# IO.net
KiCad netlist of a schematic drawn in Altium Designer
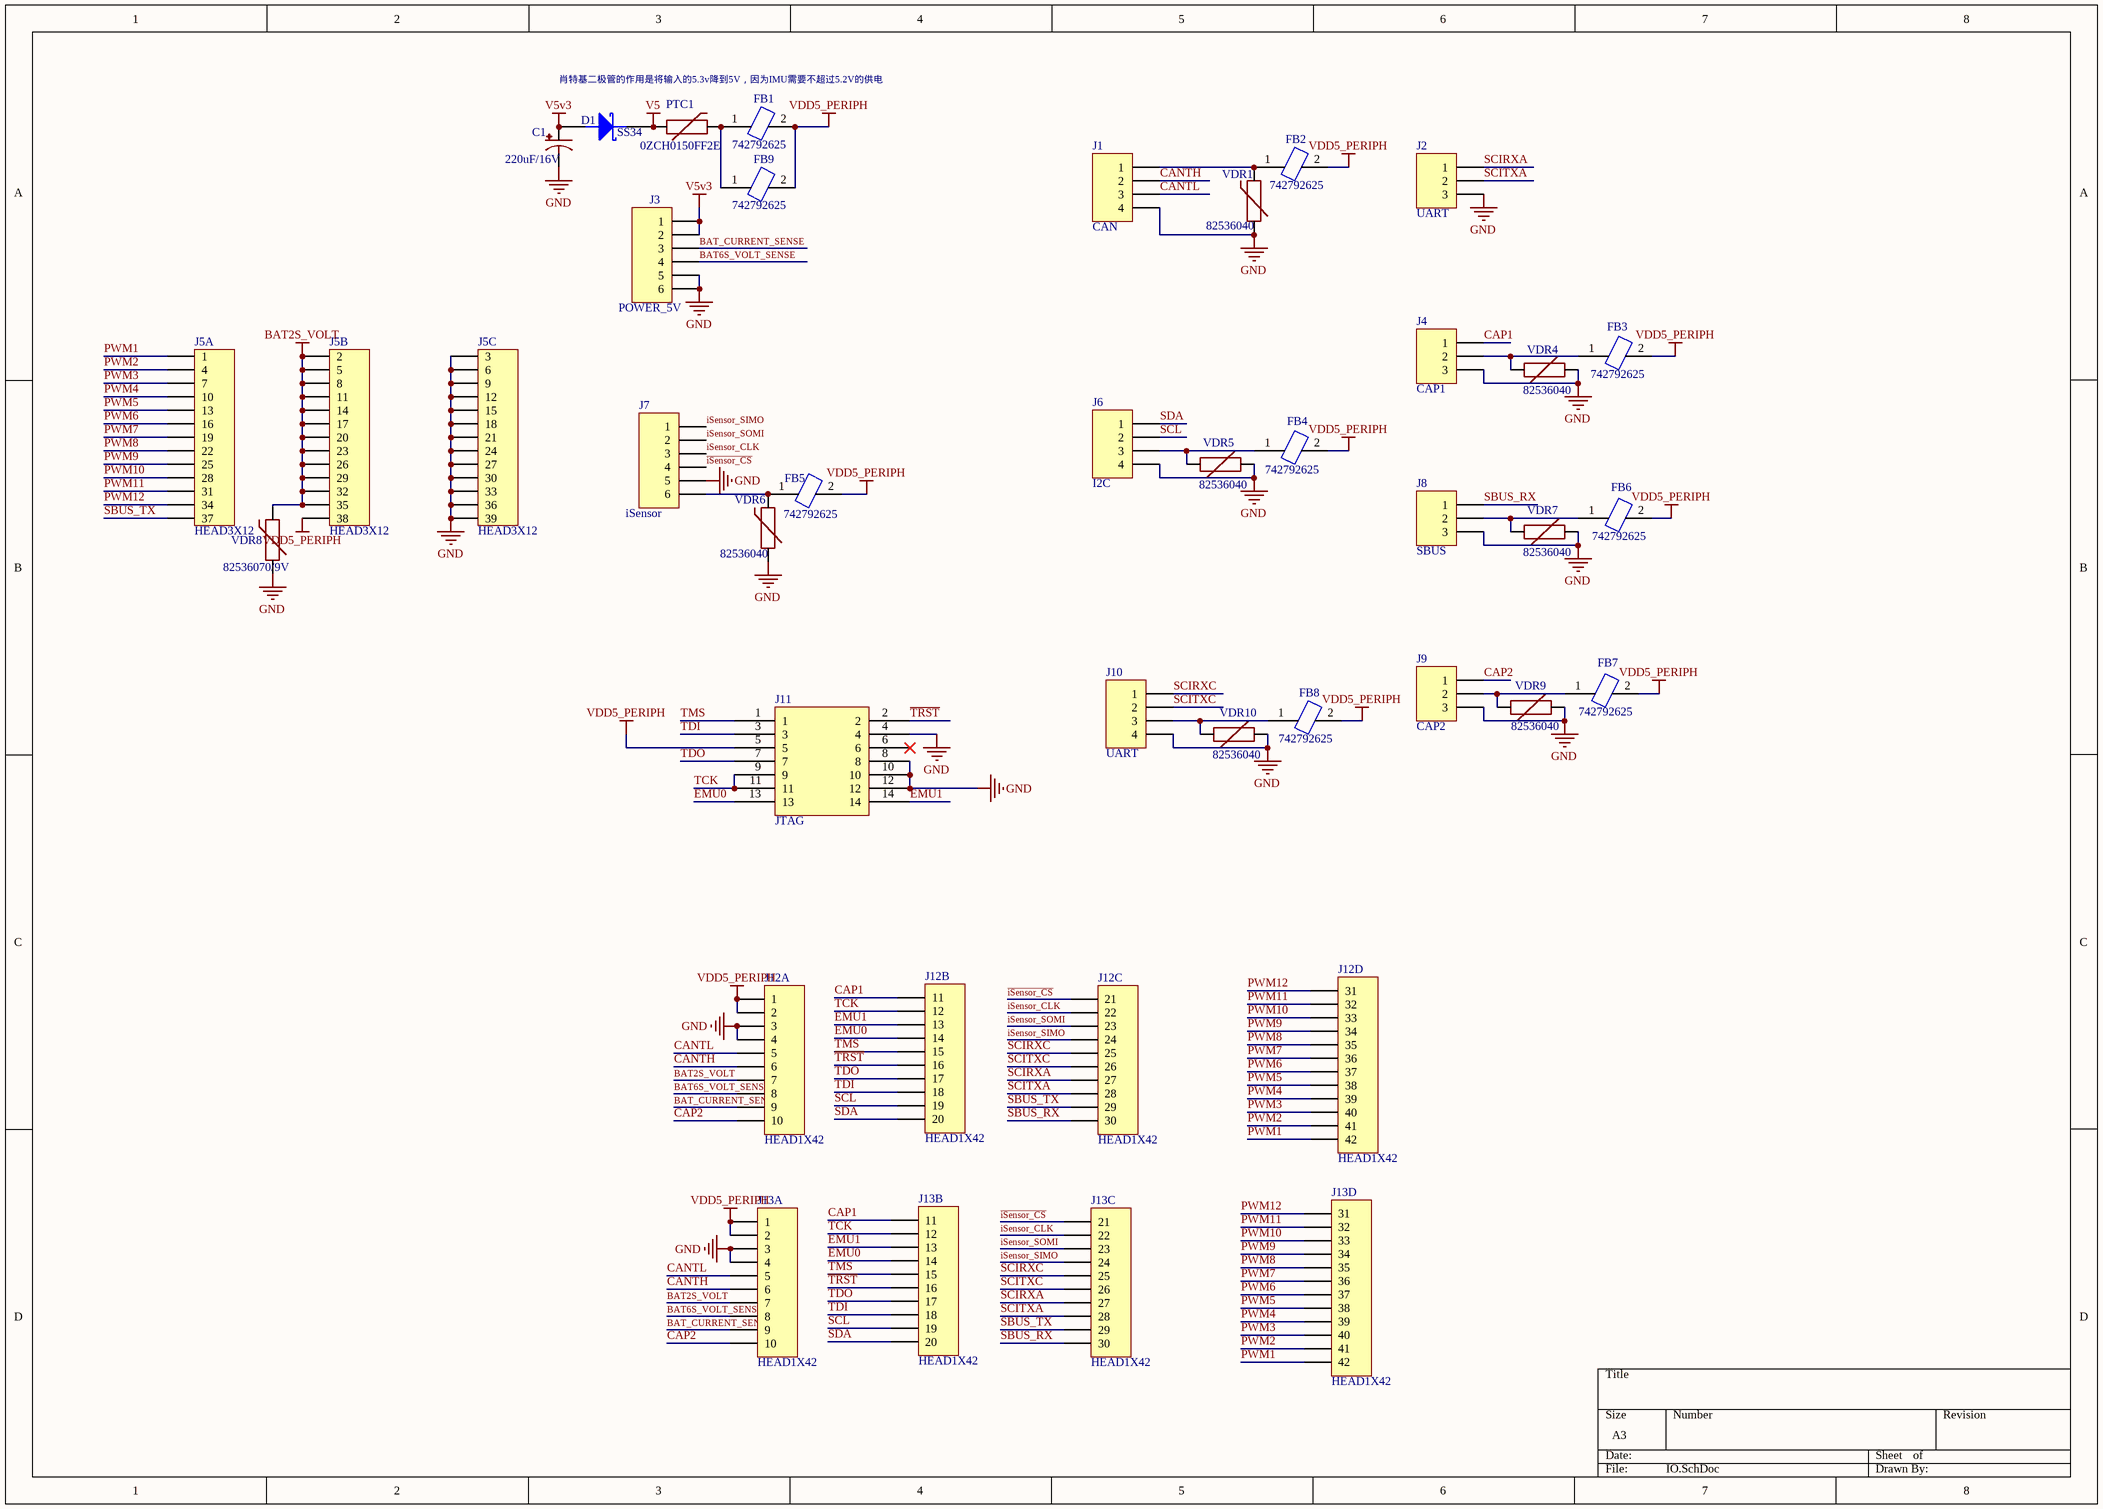
[diagram p0: IO.SchDoc]

(export (version "E")
  (design (tool "Eeschema 10.0.6"))
  (components
    (comp (ref "C1")
      (value "220uF/16V")
      (footprint "6.3*7.7/H/220u")
      (libsource (lib "研发中心原理图库文件") (part "C-POLAR"))
    )
    (comp (ref "D1")
      (value "SS34")
      (footprint "SMB/DO-214AA")
      (libsource (lib "研发中心原理图库文件") (part "DIODE SCHOTTKY"))
    )
    (comp (ref "FB1")
      (value "742792625")
      (footprint "研发中心PCB库文件:0603-FB")
      (libsource (lib "研发中心原理图库文件") (part "FB"))
    )
    (comp (ref "FB2")
      (value "742792625")
      (footprint "研发中心PCB库文件:0603-FB")
      (libsource (lib "研发中心原理图库文件") (part "FB"))
    )
    (comp (ref "FB3")
      (value "742792625")
      (footprint "研发中心PCB库文件:0603-FB")
      (libsource (lib "研发中心原理图库文件") (part "FB"))
    )
    (comp (ref "FB4")
      (value "742792625")
      (footprint "研发中心PCB库文件:0603-FB")
      (libsource (lib "研发中心原理图库文件") (part "FB"))
    )
    (comp (ref "FB5")
      (value "742792625")
      (footprint "研发中心PCB库文件:0603-FB")
      (libsource (lib "研发中心原理图库文件") (part "FB"))
    )
    (comp (ref "FB6")
      (value "742792625")
      (footprint "研发中心PCB库文件:0603-FB")
      (libsource (lib "研发中心原理图库文件") (part "FB"))
    )
    (comp (ref "FB7")
      (value "742792625")
      (footprint "研发中心PCB库文件:0603-FB")
      (libsource (lib "研发中心原理图库文件") (part "FB"))
    )
    (comp (ref "FB8")
      (value "742792625")
      (footprint "研发中心PCB库文件:0603-FB")
      (libsource (lib "研发中心原理图库文件") (part "FB"))
    )
    (comp (ref "FB9")
      (value "742792625")
      (footprint "研发中心PCB库文件:0603-FB")
      (libsource (lib "研发中心原理图库文件") (part "FB"))
    )
    (comp (ref "J1") (value "CAN") (footprint "GH1.25-4") (libsource (lib "研发中心原理图库文件") (part "HEAD1X4")))
    (comp (ref "J2") (value "UART") (footprint "SIP3") (libsource (lib "研发中心原理图库文件") (part "HEAD1X3")))
    (comp (ref "J3")
      (value "POWER_5V")
      (footprint "GH1.25-6")
      (libsource (lib "研发中心原理图库文件") (part "HEAD1X6"))
    )
    (comp (ref "J4") (value "CAP1") (footprint "SIP3") (libsource (lib "研发中心原理图库文件") (part "HEAD1X3")))
    (comp (ref "J5") (value "HEAD3X12") (footprint "3X13RA") (libsource (lib "研发中心原理图库文件") (part "HEAD3X12")))
    (comp (ref "J6") (value "I2C") (footprint "GH1.25-4") (libsource (lib "研发中心原理图库文件") (part "HEAD1X4")))
    (comp (ref "J7") (value "iSensor") (footprint "GH1.25-6") (libsource (lib "研发中心原理图库文件") (part "HEAD1X6")))
    (comp (ref "J8")
      (value "SBUS")
      (footprint "研发中心PCB库文件:SIP3")
      (libsource (lib "研发中心原理图库文件") (part "HEAD1X3"))
    )
    (comp (ref "J9") (value "CAP2") (footprint "SIP3") (libsource (lib "研发中心原理图库文件") (part "HEAD1X3")))
    (comp (ref "J10") (value "UART") (footprint "GH1.25-4") (libsource (lib "研发中心原理图库文件") (part "HEAD1X4")))
    (comp (ref "J11") (value "JTAG") (footprint "IDC14-SMT") (libsource (lib "研发中心原理图库文件") (part "IDC-14")))
    (comp (ref "J12")
      (value "HEAD1X42")
      (footprint "FPC0.5-42")
      (libsource (lib "研发中心原理图库文件") (part "HEAD1X42"))
    )
    (comp (ref "J13")
      (value "HEAD1X42")
      (footprint "FPC0.5-42")
      (libsource (lib "研发中心原理图库文件") (part "HEAD1X42"))
    )
    (comp (ref "PTC1") (value "0ZCH0150FF2E") (footprint "1210") (libsource (lib "研发中心原理图库文件") (part "PTC")))
    (comp (ref "VDR1")
      (value "82536040")
      (footprint "研发中心PCB库文件:0603R")
      (libsource (lib "研发中心原理图库文件") (part "Varistor"))
    )
    (comp (ref "VDR4")
      (value "82536040")
      (footprint "研发中心PCB库文件:0603R")
      (libsource (lib "研发中心原理图库文件") (part "Varistor"))
    )
    (comp (ref "VDR5")
      (value "82536040")
      (footprint "研发中心PCB库文件:0603R")
      (libsource (lib "研发中心原理图库文件") (part "Varistor"))
    )
    (comp (ref "VDR6")
      (value "82536040")
      (footprint "研发中心PCB库文件:0603R")
      (libsource (lib "研发中心原理图库文件") (part "Varistor"))
    )
    (comp (ref "VDR7")
      (value "82536040")
      (footprint "研发中心PCB库文件:0603R")
      (libsource (lib "研发中心原理图库文件") (part "Varistor"))
    )
    (comp (ref "VDR8")
      (value "82536070/9V")
      (footprint "0603R")
      (libsource (lib "研发中心原理图库文件") (part "Varistor"))
    )
    (comp (ref "VDR9")
      (value "82536040")
      (footprint "研发中心PCB库文件:0603R")
      (libsource (lib "研发中心原理图库文件") (part "Varistor"))
    )
    (comp (ref "VDR10")
      (value "82536040")
      (footprint "研发中心PCB库文件:0603R")
      (libsource (lib "研发中心原理图库文件") (part "Varistor"))
    )
  )
  (nets
    (net (code "1") (name "/BAT6S_VOLT_SENSE") (class "Default")
      (node (ref "J12") (pin "8") (pinfunction "8_8") (pintype "passive"))
      (node (ref "J13") (pin "8") (pinfunction "8_8") (pintype "passive"))
      (node (ref "J3") (pin "4") (pinfunction "4_4") (pintype "passive"))
    )
    (net (code "2") (name "/BAT_CURRENT_SENSE") (class "Default")
      (node (ref "J12") (pin "9") (pinfunction "9_9") (pintype "passive"))
      (node (ref "J13") (pin "9") (pinfunction "9_9") (pintype "passive"))
      (node (ref "J3") (pin "3") (pinfunction "3_3") (pintype "passive"))
    )
    (net (code "3") (name "/CANTH") (class "Default")
      (node (ref "J1") (pin "2") (pinfunction "2_2") (pintype "passive"))
      (node (ref "J12") (pin "6") (pinfunction "6_6") (pintype "passive"))
      (node (ref "J13") (pin "6") (pinfunction "6_6") (pintype "passive"))
    )
    (net (code "4") (name "/CANTL") (class "Default")
      (node (ref "J1") (pin "3") (pinfunction "3_3") (pintype "passive"))
      (node (ref "J12") (pin "5") (pinfunction "5_5") (pintype "passive"))
      (node (ref "J13") (pin "5") (pinfunction "5_5") (pintype "passive"))
    )
    (net (code "5") (name "/CAP1") (class "Default")
      (node (ref "J12") (pin "11") (pinfunction "11_11") (pintype "passive"))
      (node (ref "J13") (pin "11") (pinfunction "11_11") (pintype "passive"))
      (node (ref "J4") (pin "1") (pinfunction "1_1") (pintype "passive"))
    )
    (net (code "6") (name "/CAP2") (class "Default")
      (node (ref "J12") (pin "10") (pinfunction "10_10") (pintype "passive"))
      (node (ref "J13") (pin "10") (pinfunction "10_10") (pintype "passive"))
      (node (ref "J9") (pin "1") (pinfunction "1_1") (pintype "passive"))
    )
    (net (code "7") (name "/EMU0") (class "Default")
      (node (ref "J11") (pin "13") (pinfunction "13_13") (pintype "passive"))
      (node (ref "J12") (pin "14") (pinfunction "14_14") (pintype "passive"))
      (node (ref "J13") (pin "14") (pinfunction "14_14") (pintype "passive"))
    )
    (net (code "8") (name "/EMU1") (class "Default")
      (node (ref "J11") (pin "14") (pinfunction "14_14") (pintype "passive"))
      (node (ref "J12") (pin "13") (pinfunction "13_13") (pintype "passive"))
      (node (ref "J13") (pin "13") (pinfunction "13_13") (pintype "passive"))
    )
    (net (code "9") (name "/PWM1") (class "Default")
      (node (ref "J12") (pin "42") (pinfunction "42_42") (pintype "passive"))
      (node (ref "J13") (pin "42") (pinfunction "42_42") (pintype "passive"))
      (node (ref "J5") (pin "1") (pinfunction "1_1") (pintype "passive"))
    )
    (net (code "10") (name "/PWM2") (class "Default")
      (node (ref "J12") (pin "41") (pinfunction "41_41") (pintype "passive"))
      (node (ref "J13") (pin "41") (pinfunction "41_41") (pintype "passive"))
      (node (ref "J5") (pin "4") (pinfunction "4_4") (pintype "passive"))
    )
    (net (code "11") (name "/PWM3") (class "Default")
      (node (ref "J12") (pin "40") (pinfunction "40_40") (pintype "passive"))
      (node (ref "J13") (pin "40") (pinfunction "40_40") (pintype "passive"))
      (node (ref "J5") (pin "7") (pinfunction "7_7") (pintype "passive"))
    )
    (net (code "12") (name "/PWM4") (class "Default")
      (node (ref "J12") (pin "39") (pinfunction "39_39") (pintype "passive"))
      (node (ref "J13") (pin "39") (pinfunction "39_39") (pintype "passive"))
      (node (ref "J5") (pin "10") (pinfunction "10_10") (pintype "passive"))
    )
    (net (code "13") (name "/PWM5") (class "Default")
      (node (ref "J12") (pin "38") (pinfunction "38_38") (pintype "passive"))
      (node (ref "J13") (pin "38") (pinfunction "38_38") (pintype "passive"))
      (node (ref "J5") (pin "13") (pinfunction "13_13") (pintype "passive"))
    )
    (net (code "14") (name "/PWM6") (class "Default")
      (node (ref "J12") (pin "37") (pinfunction "37_37") (pintype "passive"))
      (node (ref "J13") (pin "37") (pinfunction "37_37") (pintype "passive"))
      (node (ref "J5") (pin "16") (pinfunction "16_16") (pintype "passive"))
    )
    (net (code "15") (name "/PWM7") (class "Default")
      (node (ref "J12") (pin "36") (pinfunction "36_36") (pintype "passive"))
      (node (ref "J13") (pin "36") (pinfunction "36_36") (pintype "passive"))
      (node (ref "J5") (pin "19") (pinfunction "19_19") (pintype "passive"))
    )
    (net (code "16") (name "/PWM8") (class "Default")
      (node (ref "J12") (pin "35") (pinfunction "35_35") (pintype "passive"))
      (node (ref "J13") (pin "35") (pinfunction "35_35") (pintype "passive"))
      (node (ref "J5") (pin "22") (pinfunction "22_22") (pintype "passive"))
    )
    (net (code "17") (name "/PWM9") (class "Default")
      (node (ref "J12") (pin "34") (pinfunction "34_34") (pintype "passive"))
      (node (ref "J13") (pin "34") (pinfunction "34_34") (pintype "passive"))
      (node (ref "J5") (pin "25") (pinfunction "25_25") (pintype "passive"))
    )
    (net (code "18") (name "/PWM10") (class "Default")
      (node (ref "J12") (pin "33") (pinfunction "33_33") (pintype "passive"))
      (node (ref "J13") (pin "33") (pinfunction "33_33") (pintype "passive"))
      (node (ref "J5") (pin "28") (pinfunction "28_28") (pintype "passive"))
    )
    (net (code "19") (name "/PWM11") (class "Default")
      (node (ref "J12") (pin "32") (pinfunction "32_32") (pintype "passive"))
      (node (ref "J13") (pin "32") (pinfunction "32_32") (pintype "passive"))
      (node (ref "J5") (pin "31") (pinfunction "31_31") (pintype "passive"))
    )
    (net (code "20") (name "/PWM12") (class "Default")
      (node (ref "J12") (pin "31") (pinfunction "31_31") (pintype "passive"))
      (node (ref "J13") (pin "31") (pinfunction "31_31") (pintype "passive"))
      (node (ref "J5") (pin "34") (pinfunction "34_34") (pintype "passive"))
    )
    (net (code "21") (name "/SBUS_RX") (class "Default")
      (node (ref "J12") (pin "30") (pinfunction "30_30") (pintype "passive"))
      (node (ref "J13") (pin "30") (pinfunction "30_30") (pintype "passive"))
      (node (ref "J8") (pin "1") (pinfunction "1_1") (pintype "passive"))
    )
    (net (code "22") (name "/SBUS_TX") (class "Default")
      (node (ref "J12") (pin "29") (pinfunction "29_29") (pintype "passive"))
      (node (ref "J13") (pin "29") (pinfunction "29_29") (pintype "passive"))
      (node (ref "J5") (pin "37") (pinfunction "37_37") (pintype "passive"))
    )
    (net (code "23") (name "/SCIRXA") (class "Default")
      (node (ref "J12") (pin "27") (pinfunction "27_27") (pintype "passive"))
      (node (ref "J13") (pin "27") (pinfunction "27_27") (pintype "passive"))
      (node (ref "J2") (pin "1") (pinfunction "1_1") (pintype "passive"))
    )
    (net (code "24") (name "/SCIRXC") (class "Default")
      (node (ref "J10") (pin "1") (pinfunction "1_1") (pintype "passive"))
      (node (ref "J12") (pin "25") (pinfunction "25_25") (pintype "passive"))
      (node (ref "J13") (pin "25") (pinfunction "25_25") (pintype "passive"))
    )
    (net (code "25") (name "/SCITXA") (class "Default")
      (node (ref "J12") (pin "28") (pinfunction "28_28") (pintype "passive"))
      (node (ref "J13") (pin "28") (pinfunction "28_28") (pintype "passive"))
      (node (ref "J2") (pin "2") (pinfunction "2_2") (pintype "passive"))
    )
    (net (code "26") (name "/SCITXC") (class "Default")
      (node (ref "J10") (pin "2") (pinfunction "2_2") (pintype "passive"))
      (node (ref "J12") (pin "26") (pinfunction "26_26") (pintype "passive"))
      (node (ref "J13") (pin "26") (pinfunction "26_26") (pintype "passive"))
    )
    (net (code "27") (name "/SCL") (class "Default")
      (node (ref "J12") (pin "19") (pinfunction "19_19") (pintype "passive"))
      (node (ref "J13") (pin "19") (pinfunction "19_19") (pintype "passive"))
      (node (ref "J6") (pin "2") (pinfunction "2_2") (pintype "passive"))
    )
    (net (code "28") (name "/SDA") (class "Default")
      (node (ref "J12") (pin "20") (pinfunction "20_20") (pintype "passive"))
      (node (ref "J13") (pin "20") (pinfunction "20_20") (pintype "passive"))
      (node (ref "J6") (pin "1") (pinfunction "1_1") (pintype "passive"))
    )
    (net (code "29") (name "/TCK") (class "Default")
      (node (ref "J11") (pin "11") (pinfunction "11_11") (pintype "passive"))
      (node (ref "J11") (pin "9") (pinfunction "9_9") (pintype "passive"))
      (node (ref "J12") (pin "12") (pinfunction "12_12") (pintype "passive"))
      (node (ref "J13") (pin "12") (pinfunction "12_12") (pintype "passive"))
    )
    (net (code "30") (name "/TDI") (class "Default")
      (node (ref "J11") (pin "3") (pinfunction "3_3") (pintype "passive"))
      (node (ref "J12") (pin "18") (pinfunction "18_18") (pintype "passive"))
      (node (ref "J13") (pin "18") (pinfunction "18_18") (pintype "passive"))
    )
    (net (code "31") (name "/TDO") (class "Default")
      (node (ref "J11") (pin "7") (pinfunction "7_7") (pintype "passive"))
      (node (ref "J12") (pin "17") (pinfunction "17_17") (pintype "passive"))
      (node (ref "J13") (pin "17") (pinfunction "17_17") (pintype "passive"))
    )
    (net (code "32") (name "/TMS") (class "Default")
      (node (ref "J11") (pin "1") (pinfunction "1_1") (pintype "passive"))
      (node (ref "J12") (pin "15") (pinfunction "15_15") (pintype "passive"))
      (node (ref "J13") (pin "15") (pinfunction "15_15") (pintype "passive"))
    )
    (net (code "33") (name "/iSensor_CLK") (class "Default")
      (node (ref "J12") (pin "22") (pinfunction "22_22") (pintype "passive"))
      (node (ref "J13") (pin "22") (pinfunction "22_22") (pintype "passive"))
      (node (ref "J7") (pin "3") (pinfunction "3_3") (pintype "passive"))
    )
    (net (code "34") (name "/iSensor_SIMO") (class "Default")
      (node (ref "J12") (pin "24") (pinfunction "24_24") (pintype "passive"))
      (node (ref "J13") (pin "24") (pinfunction "24_24") (pintype "passive"))
      (node (ref "J7") (pin "1") (pinfunction "1_1") (pintype "passive"))
    )
    (net (code "35") (name "/iSensor_SOMI") (class "Default")
      (node (ref "J12") (pin "23") (pinfunction "23_23") (pintype "passive"))
      (node (ref "J13") (pin "23") (pinfunction "23_23") (pintype "passive"))
      (node (ref "J7") (pin "2") (pinfunction "2_2") (pintype "passive"))
    )
    (net (code "36") (name "/~{TRST}") (class "Default")
      (node (ref "J11") (pin "2") (pinfunction "2_2") (pintype "passive"))
      (node (ref "J12") (pin "16") (pinfunction "16_16") (pintype "passive"))
      (node (ref "J13") (pin "16") (pinfunction "16_16") (pintype "passive"))
    )
    (net (code "37") (name "/~{iSensor_CS}") (class "Default")
      (node (ref "J12") (pin "21") (pinfunction "21_21") (pintype "passive"))
      (node (ref "J13") (pin "21") (pinfunction "21_21") (pintype "passive"))
      (node (ref "J7") (pin "4") (pinfunction "4_4") (pintype "passive"))
    )
    (net (code "38") (name "BAT2S_VOLT") (class "Default")
      (node (ref "J12") (pin "7") (pinfunction "7_7") (pintype "passive"))
      (node (ref "J13") (pin "7") (pinfunction "7_7") (pintype "passive"))
      (node (ref "J5") (pin "11") (pinfunction "11_11") (pintype "passive"))
      (node (ref "J5") (pin "14") (pinfunction "14_14") (pintype "passive"))
      (node (ref "J5") (pin "17") (pinfunction "17_17") (pintype "passive"))
      (node (ref "J5") (pin "2") (pinfunction "2_2") (pintype "passive"))
      (node (ref "J5") (pin "20") (pinfunction "20_20") (pintype "passive"))
      (node (ref "J5") (pin "23") (pinfunction "23_23") (pintype "passive"))
      (node (ref "J5") (pin "26") (pinfunction "26_26") (pintype "passive"))
      (node (ref "J5") (pin "29") (pinfunction "29_29") (pintype "passive"))
      (node (ref "J5") (pin "32") (pinfunction "32_32") (pintype "passive"))
      (node (ref "J5") (pin "35") (pinfunction "35_35") (pintype "passive"))
      (node (ref "J5") (pin "5") (pinfunction "5_5") (pintype "passive"))
      (node (ref "J5") (pin "8") (pinfunction "8_8") (pintype "passive"))
      (node (ref "VDR8") (pin "2") (pinfunction "2_2") (pintype "passive"))
    )
    (net (code "39") (name "GND") (class "Default")
      (node (ref "C1") (pin "2") (pinfunction "2_2") (pintype "passive"))
      (node (ref "J1") (pin "4") (pinfunction "4_4") (pintype "passive"))
      (node (ref "J10") (pin "4") (pinfunction "4_4") (pintype "passive"))
      (node (ref "J11") (pin "10") (pinfunction "10_10") (pintype "passive"))
      (node (ref "J11") (pin "12") (pinfunction "12_12") (pintype "passive"))
      (node (ref "J11") (pin "4") (pinfunction "4_4") (pintype "passive"))
      (node (ref "J11") (pin "8") (pinfunction "8_8") (pintype "passive"))
      (node (ref "J12") (pin "3") (pinfunction "3_3") (pintype "passive"))
      (node (ref "J12") (pin "4") (pinfunction "4_4") (pintype "passive"))
      (node (ref "J13") (pin "3") (pinfunction "3_3") (pintype "passive"))
      (node (ref "J13") (pin "4") (pinfunction "4_4") (pintype "passive"))
      (node (ref "J2") (pin "3") (pinfunction "3_3") (pintype "passive"))
      (node (ref "J3") (pin "5") (pinfunction "5_5") (pintype "passive"))
      (node (ref "J3") (pin "6") (pinfunction "6_6") (pintype "passive"))
      (node (ref "J4") (pin "3") (pinfunction "3_3") (pintype "passive"))
      (node (ref "J5") (pin "12") (pinfunction "12_12") (pintype "passive"))
      (node (ref "J5") (pin "15") (pinfunction "15_15") (pintype "passive"))
      (node (ref "J5") (pin "18") (pinfunction "18_18") (pintype "passive"))
      (node (ref "J5") (pin "21") (pinfunction "21_21") (pintype "passive"))
      (node (ref "J5") (pin "24") (pinfunction "24_24") (pintype "passive"))
      (node (ref "J5") (pin "27") (pinfunction "27_27") (pintype "passive"))
      (node (ref "J5") (pin "3") (pinfunction "3_3") (pintype "passive"))
      (node (ref "J5") (pin "30") (pinfunction "30_30") (pintype "passive"))
      (node (ref "J5") (pin "33") (pinfunction "33_33") (pintype "passive"))
      (node (ref "J5") (pin "36") (pinfunction "36_36") (pintype "passive"))
      (node (ref "J5") (pin "39") (pinfunction "39_39") (pintype "passive"))
      (node (ref "J5") (pin "6") (pinfunction "6_6") (pintype "passive"))
      (node (ref "J5") (pin "9") (pinfunction "9_9") (pintype "passive"))
      (node (ref "J6") (pin "4") (pinfunction "4_4") (pintype "passive"))
      (node (ref "J7") (pin "5") (pinfunction "5_5") (pintype "passive"))
      (node (ref "J8") (pin "3") (pinfunction "3_3") (pintype "passive"))
      (node (ref "J9") (pin "3") (pinfunction "3_3") (pintype "passive"))
      (node (ref "VDR1") (pin "1") (pinfunction "1_1") (pintype "passive"))
      (node (ref "VDR10") (pin "1") (pinfunction "1_1") (pintype "passive"))
      (node (ref "VDR4") (pin "2") (pinfunction "2_2") (pintype "passive"))
      (node (ref "VDR5") (pin "1") (pinfunction "1_1") (pintype "passive"))
      (node (ref "VDR6") (pin "1") (pinfunction "1_1") (pintype "passive"))
      (node (ref "VDR7") (pin "1") (pinfunction "1_1") (pintype "passive"))
      (node (ref "VDR8") (pin "1") (pinfunction "1_1") (pintype "passive"))
      (node (ref "VDR9") (pin "1") (pinfunction "1_1") (pintype "passive"))
    )
    (net (code "40") (name "Net-(FB1-Pad1)") (class "Default")
      (node (ref "FB1") (pin "1") (pinfunction "1_1") (pintype "passive"))
      (node (ref "FB9") (pin "1") (pinfunction "1_1") (pintype "passive"))
      (node (ref "PTC1") (pin "2") (pinfunction "2_2") (pintype "passive"))
    )
    (net (code "41") (name "Net-(FB2-Pad1)") (class "Default")
      (node (ref "FB2") (pin "1") (pinfunction "1_1") (pintype "passive"))
      (node (ref "J1") (pin "1") (pinfunction "1_1") (pintype "passive"))
      (node (ref "VDR1") (pin "2") (pinfunction "2_2") (pintype "passive"))
    )
    (net (code "42") (name "Net-(FB3-Pad1)") (class "Default")
      (node (ref "FB3") (pin "1") (pinfunction "1_1") (pintype "passive"))
      (node (ref "J4") (pin "2") (pinfunction "2_2") (pintype "passive"))
      (node (ref "VDR4") (pin "1") (pinfunction "1_1") (pintype "passive"))
    )
    (net (code "43") (name "Net-(FB4-Pad1)") (class "Default")
      (node (ref "FB4") (pin "1") (pinfunction "1_1") (pintype "passive"))
      (node (ref "J6") (pin "3") (pinfunction "3_3") (pintype "passive"))
      (node (ref "VDR5") (pin "2") (pinfunction "2_2") (pintype "passive"))
    )
    (net (code "44") (name "Net-(FB5-Pad1)") (class "Default")
      (node (ref "FB5") (pin "1") (pinfunction "1_1") (pintype "passive"))
      (node (ref "J7") (pin "6") (pinfunction "6_6") (pintype "passive"))
      (node (ref "VDR6") (pin "2") (pinfunction "2_2") (pintype "passive"))
    )
    (net (code "45") (name "Net-(FB6-Pad1)") (class "Default")
      (node (ref "FB6") (pin "1") (pinfunction "1_1") (pintype "passive"))
      (node (ref "J8") (pin "2") (pinfunction "2_2") (pintype "passive"))
      (node (ref "VDR7") (pin "2") (pinfunction "2_2") (pintype "passive"))
    )
    (net (code "46") (name "Net-(FB7-Pad1)") (class "Default")
      (node (ref "FB7") (pin "1") (pinfunction "1_1") (pintype "passive"))
      (node (ref "J9") (pin "2") (pinfunction "2_2") (pintype "passive"))
      (node (ref "VDR9") (pin "2") (pinfunction "2_2") (pintype "passive"))
    )
    (net (code "47") (name "Net-(FB8-Pad1)") (class "Default")
      (node (ref "FB8") (pin "1") (pinfunction "1_1") (pintype "passive"))
      (node (ref "J10") (pin "3") (pinfunction "3_3") (pintype "passive"))
      (node (ref "VDR10") (pin "2") (pinfunction "2_2") (pintype "passive"))
    )
    (net (code "48") (name "V5") (class "Default")
      (node (ref "D1") (pin "2") (pinfunction "2_2") (pintype "passive"))
      (node (ref "PTC1") (pin "1") (pinfunction "1_1") (pintype "passive"))
    )
    (net (code "49") (name "V5v3") (class "Default")
      (node (ref "C1") (pin "1") (pinfunction "1_1") (pintype "passive"))
      (node (ref "D1") (pin "1") (pinfunction "1_1") (pintype "passive"))
      (node (ref "J3") (pin "1") (pinfunction "1_1") (pintype "passive"))
      (node (ref "J3") (pin "2") (pinfunction "2_2") (pintype "passive"))
    )
    (net (code "50") (name "VDD5_PERIPH") (class "Default")
      (node (ref "FB1") (pin "2") (pinfunction "2_2") (pintype "passive"))
      (node (ref "FB2") (pin "2") (pinfunction "2_2") (pintype "passive"))
      (node (ref "FB3") (pin "2") (pinfunction "2_2") (pintype "passive"))
      (node (ref "FB4") (pin "2") (pinfunction "2_2") (pintype "passive"))
      (node (ref "FB5") (pin "2") (pinfunction "2_2") (pintype "passive"))
      (node (ref "FB6") (pin "2") (pinfunction "2_2") (pintype "passive"))
      (node (ref "FB7") (pin "2") (pinfunction "2_2") (pintype "passive"))
      (node (ref "FB8") (pin "2") (pinfunction "2_2") (pintype "passive"))
      (node (ref "FB9") (pin "2") (pinfunction "2_2") (pintype "passive"))
      (node (ref "J11") (pin "5") (pinfunction "5_5") (pintype "passive"))
      (node (ref "J12") (pin "1") (pinfunction "1_1") (pintype "passive"))
      (node (ref "J12") (pin "2") (pinfunction "2_2") (pintype "passive"))
      (node (ref "J13") (pin "1") (pinfunction "1_1") (pintype "passive"))
      (node (ref "J13") (pin "2") (pinfunction "2_2") (pintype "passive"))
      (node (ref "J5") (pin "38") (pinfunction "38_38") (pintype "passive"))
    )
    (net (code "51") (name "unconnected-(J11-Pad6)") (class "Default")
      (node (ref "J11") (pin "6") (pinfunction "6_6") (pintype "passive+no_connect"))
    )
  )
)
